# MiniRacer_V2.net
KiCad netlist of a schematic drawn in Altium Designer
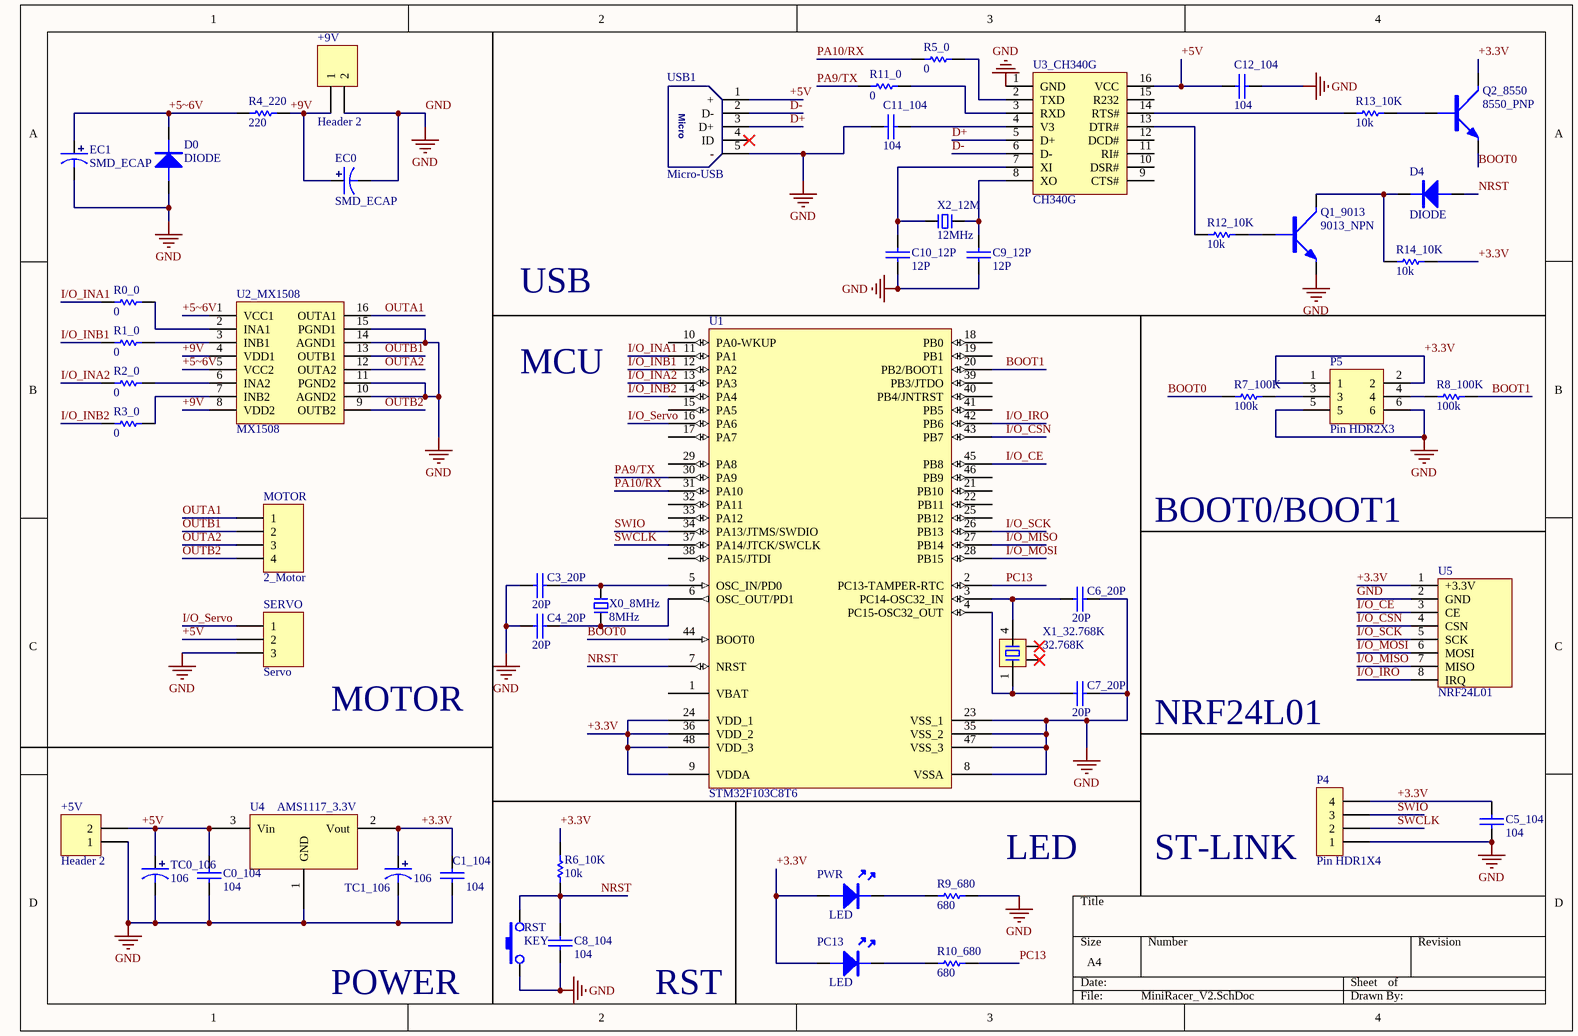
[diagram p0: MiniRacer_V2.SchDoc]

(export (version "E")
  (design (tool "Eeschema 10.0.6"))
  (components
    (comp (ref "+5V")
      (value "Header 2")
      (footprint "HDR1X2")
      (description "Header, 2-Pin")
      (fields (field (name "PUBLISHER") "Altium Limited"))
      (libsource (lib "Miscellaneous Connectors") (part "Header 2"))
    )
    (comp (ref "+9V")
      (value "Header 2")
      (footprint "HDR1X2")
      (description "Header, 2-Pin")
      (fields (field (name "PUBLISHER") "Altium Limited"))
      (libsource (lib "") (part "Header 2_1"))
    )
    (comp (ref "C0_104")
      (value "104")
      (footprint "0603C")
      (description "无极性电容")
      (libsource (lib "电容") (part "CAP"))
    )
    (comp (ref "C1_104")
      (value "104")
      (footprint "0603C")
      (description "无极性电容")
      (libsource (lib "电容") (part "CAP"))
    )
    (comp (ref "C3_20P")
      (value "20P")
      (footprint "0603C")
      (description "无极性电容")
      (libsource (lib "电容") (part "CAP"))
    )
    (comp (ref "C4_20P")
      (value "20P")
      (footprint "0603C")
      (description "无极性电容")
      (libsource (lib "电容") (part "CAP"))
    )
    (comp (ref "C5_104")
      (value "104")
      (footprint "0603C")
      (description "无极性电容")
      (libsource (lib "电容") (part "CAP"))
    )
    (comp (ref "C6_20P")
      (value "20P")
      (footprint "0603C")
      (description "无极性电容")
      (libsource (lib "电容") (part "CAP"))
    )
    (comp (ref "C7_20P")
      (value "20P")
      (footprint "0603C")
      (description "无极性电容")
      (libsource (lib "电容") (part "CAP"))
    )
    (comp (ref "C8_104")
      (value "104")
      (footprint "0603C")
      (description "无极性电容")
      (libsource (lib "电容") (part "CAP"))
    )
    (comp (ref "C9_12P")
      (value "12P")
      (footprint "0603C")
      (description "无极性电容")
      (libsource (lib "电容") (part "CAP"))
    )
    (comp (ref "C10_12P")
      (value "12P")
      (footprint "0603C")
      (description "无极性电容")
      (libsource (lib "电容") (part "CAP"))
    )
    (comp (ref "C11_104")
      (value "104")
      (footprint "0603C")
      (description "无极性电容")
      (libsource (lib "电容") (part "CAP"))
    )
    (comp (ref "C12_104")
      (value "104")
      (footprint "0603C")
      (description "无极性电容")
      (libsource (lib "电容") (part "CAP"))
    )
    (comp (ref "D0")
      (value "DIODE")
      (footprint "LL34")
      (description "普通二极管")
      (libsource (lib "二极管") (part "DIODE"))
    )
    (comp (ref "D4")
      (value "DIODE")
      (footprint "SOD-123")
      (description "普通二极管")
      (libsource (lib "二极管") (part "DIODE"))
    )
    (comp (ref "EC0")
      (value "SMD_ECAP")
      (footprint "SMD-EC6.3X6.3X10")
      (description "贴片电解电容")
      (libsource (lib "电容") (part "SMD_ECAP"))
    )
    (comp (ref "EC1")
      (value "SMD_ECAP")
      (footprint "SMD-EC6.3X6.3X10")
      (description "贴片电解电容")
      (libsource (lib "电容") (part "SMD_ECAP"))
    )
    (comp (ref "MOTOR")
      (value "2_Motor")
      (footprint "HDR1X4")
      (description "Header, 4-Pin")
      (fields (field (name "PUBLISHER") "Altium Limited"))
      (libsource (lib "Miscellaneous Connectors") (part "Header 4"))
    )
    (comp (ref "P4") (value "Pin HDR1X4") (footprint "HDR1X4") (libsource (lib "排针") (part "Pin HDR1X4")))
    (comp (ref "P5")
      (value "Pin HDR2X3")
      (footprint "Pin HDR2X3/2.54mm-S")
      (libsource (lib "排针") (part "Pin HDR2X3"))
    )
    (comp (ref "PC13") (value "LED") (footprint "LED-0603Y") (libsource (lib "LED") (part "LED")))
    (comp (ref "PWR") (value "LED") (footprint "LED-0603Y") (libsource (lib "LED") (part "LED")))
    (comp (ref "Q1_9013")
      (value "9013_NPN")
      (footprint "SOT-23")
      (description "NPN三极管")
      (libsource (lib "三极管") (part "NPN"))
    )
    (comp (ref "Q2_8550")
      (value "8550_PNP")
      (footprint "SOT-23")
      (description "NPN三极管")
      (libsource (lib "三极管") (part "NPN"))
    )
    (comp (ref "R0_0") (value "0") (footprint "0603R") (libsource (lib "电阻") (part "RES")))
    (comp (ref "R1_0") (value "0") (footprint "0603R") (libsource (lib "电阻") (part "RES")))
    (comp (ref "R2_0") (value "0") (footprint "0603R") (libsource (lib "电阻") (part "RES")))
    (comp (ref "R3_0") (value "0") (footprint "0603R") (libsource (lib "电阻") (part "RES")))
    (comp (ref "R4_220") (value "220") (footprint "0603R") (libsource (lib "电阻") (part "RES")))
    (comp (ref "R5_0") (value "0") (footprint "0603R") (libsource (lib "电阻") (part "RES")))
    (comp (ref "R6_10K") (value "10k") (footprint "0603R") (libsource (lib "电阻") (part "RES")))
    (comp (ref "R7_100K") (value "100k") (footprint "0603R") (libsource (lib "电阻") (part "RES")))
    (comp (ref "R8_100K") (value "100k") (footprint "0603R") (libsource (lib "电阻") (part "RES")))
    (comp (ref "R9_680") (value "680") (footprint "0603R") (libsource (lib "电阻") (part "RES")))
    (comp (ref "R10_680") (value "680") (footprint "0603R") (libsource (lib "电阻") (part "RES")))
    (comp (ref "R11_0") (value "0") (footprint "0603R") (libsource (lib "电阻") (part "RES")))
    (comp (ref "R12_10K") (value "10k") (footprint "0603R") (libsource (lib "电阻") (part "RES")))
    (comp (ref "R13_10K") (value "10k") (footprint "0603R") (libsource (lib "电阻") (part "RES")))
    (comp (ref "R14_10K") (value "10k") (footprint "0603R") (libsource (lib "电阻") (part "RES")))
    (comp (ref "RST") (value "KEY") (footprint "SMD-3X6X2.5") (libsource (lib "轻触开关") (part "KEY")))
    (comp (ref "SERVO")
      (value "Servo")
      (footprint "HDR1X3")
      (description "Header, 3-Pin")
      (fields (field (name "PUBLISHER") "Altium Limited"))
      (libsource (lib "Miscellaneous Connectors") (part "Header 3"))
    )
    (comp (ref "TC0_106")
      (value "106")
      (footprint "TAJ-A/3216")
      (description "钽电容")
      (libsource (lib "电容") (part "TCAP"))
    )
    (comp (ref "TC1_106")
      (value "106")
      (footprint "TAJ-A/3216")
      (description "钽电容")
      (libsource (lib "电容") (part "TCAP"))
    )
    (comp (ref "U1")
      (value "STM32F103C8T6")
      (footprint "LQFP48 7X7")
      (libsource (lib "STM32系列") (part "STM32F103C8T6"))
    )
    (comp (ref "U2_MX1508") (value "MX1508") (footprint "SOP16") (libsource (lib "未分类IC") (part "MX1508")))
    (comp (ref "U3_CH340G") (value "CH340G") (footprint "SOP16") (libsource (lib "未分类IC") (part "CH340G")))
    (comp (ref "U4")
      (value "AMS1117_3.3V")
      (footprint "SOT223")
      (description "三端稳压芯片")
      (libsource (lib "电源芯片") (part "AMS1117"))
    )
    (comp (ref "U5") (value "NRF24L01") (footprint "NRF24L01") (libsource (lib "未分类IC") (part "NRF24L01")))
    (comp (ref "USB1")
      (value "Micro-USB")
      (footprint "USB-MICRO_A")
      (libsource (lib "USB") (part "Micro-USB"))
    )
    (comp (ref "X0_8MHz")
      (value "8MHz")
      (footprint "OSC 5032-2P")
      (description "2脚无源脚晶振")
      (libsource (lib "晶振") (part "XTAL-2P"))
    )
    (comp (ref "X1_32.768K")
      (value "32.768K")
      (footprint "OSC MC-306")
      (description "MC系列4脚晶振")
      (libsource (lib "晶振") (part "XTAL-MC-4P"))
    )
    (comp (ref "X2_12M")
      (value "12MHz")
      (footprint "OSC 5032-2P")
      (description "2脚无源脚晶振")
      (libsource (lib "晶振") (part "XTAL-2P"))
    )
  )
  (nets
    (net (code "1") (name "/+3.3V") (class "Default")
      (node (ref "C1_104") (pin "2") (pinfunction "2_2") (pintype "passive"))
      (node (ref "C5_104") (pin "1") (pinfunction "1_1") (pintype "passive"))
      (node (ref "P4") (pin "4") (pinfunction "4_4") (pintype "passive"))
      (node (ref "P5") (pin "1") (pinfunction "1_1") (pintype "passive"))
      (node (ref "P5") (pin "2") (pinfunction "2_2") (pintype "passive"))
      (node (ref "PC13") (pin "A") (pinfunction "A_A") (pintype "passive"))
      (node (ref "PWR") (pin "A") (pinfunction "A_A") (pintype "passive"))
      (node (ref "Q2_8550") (pin "C") (pinfunction "C_C") (pintype "passive"))
      (node (ref "R14_10K") (pin "2") (pinfunction "2_2") (pintype "passive"))
      (node (ref "R6_10K") (pin "2") (pinfunction "2_2") (pintype "passive"))
      (node (ref "TC1_106") (pin "1") (pinfunction "1_1") (pintype "passive"))
      (node (ref "U1") (pin "24") (pinfunction "VDD_1_24") (pintype "power_in"))
      (node (ref "U1") (pin "36") (pinfunction "VDD_2_36") (pintype "power_in"))
      (node (ref "U1") (pin "48") (pinfunction "VDD_3_48") (pintype "power_in"))
      (node (ref "U1") (pin "9") (pinfunction "VDDA_9") (pintype "power_in"))
      (node (ref "U4") (pin "2") (pinfunction "Vout_2") (pintype "passive"))
      (node (ref "U5") (pin "1") (pinfunction "+3.3V_1") (pintype "passive"))
    )
    (net (code "2") (name "/+5V") (class "Default")
      (node (ref "+5V") (pin "2") (pinfunction "2_2") (pintype "passive"))
      (node (ref "C0_104") (pin "2") (pinfunction "2_2") (pintype "passive"))
      (node (ref "C12_104") (pin "2") (pinfunction "2_2") (pintype "passive"))
      (node (ref "SERVO") (pin "2") (pinfunction "2_2") (pintype "passive"))
      (node (ref "TC0_106") (pin "1") (pinfunction "1_1") (pintype "passive"))
      (node (ref "U3_CH340G") (pin "16") (pinfunction "VCC_16") (pintype "passive"))
      (node (ref "U4") (pin "3") (pinfunction "Vin_3") (pintype "passive"))
      (node (ref "USB1") (pin "1") (pinfunction "+_1") (pintype "passive"))
    )
    (net (code "3") (name "/+5~6V") (class "Default")
      (node (ref "D0") (pin "K") (pinfunction "K_K") (pintype "passive"))
      (node (ref "EC1") (pin "1") (pinfunction "1_1") (pintype "passive"))
      (node (ref "R4_220") (pin "1") (pinfunction "1_1") (pintype "passive"))
      (node (ref "U2_MX1508") (pin "1") (pinfunction "VCC1_1") (pintype "passive"))
      (node (ref "U2_MX1508") (pin "5") (pinfunction "VCC2_5") (pintype "passive"))
    )
    (net (code "4") (name "/+9V") (class "Default")
      (node (ref "+9V") (pin "1") (pinfunction "1_1") (pintype "passive"))
      (node (ref "EC0") (pin "1") (pinfunction "1_1") (pintype "passive"))
      (node (ref "R4_220") (pin "2") (pinfunction "2_2") (pintype "passive"))
      (node (ref "U2_MX1508") (pin "4") (pinfunction "VDD1_4") (pintype "passive"))
      (node (ref "U2_MX1508") (pin "8") (pinfunction "VDD2_8") (pintype "passive"))
    )
    (net (code "5") (name "/BOOT0") (class "Default")
      (node (ref "Q2_8550") (pin "E") (pinfunction "E_E") (pintype "passive"))
      (node (ref "R7_100K") (pin "2") (pinfunction "2_2") (pintype "passive"))
      (node (ref "U1") (pin "44") (pinfunction "BOOT0_44") (pintype "input"))
    )
    (net (code "6") (name "/BOOT1") (class "Default")
      (node (ref "R8_100K") (pin "1") (pinfunction "1_1") (pintype "passive"))
      (node (ref "U1") (pin "20") (pinfunction "PB2/BOOT1_20") (pintype "bidirectional"))
    )
    (net (code "7") (name "/D+") (class "Default")
      (node (ref "U3_CH340G") (pin "5") (pinfunction "D+_5") (pintype "passive"))
      (node (ref "USB1") (pin "3") (pinfunction "D+_3") (pintype "passive"))
    )
    (net (code "8") (name "/D-") (class "Default")
      (node (ref "U3_CH340G") (pin "6") (pinfunction "D-_6") (pintype "passive"))
      (node (ref "USB1") (pin "2") (pinfunction "D-_2") (pintype "passive"))
    )
    (net (code "9") (name "/I{slash}O_CE") (class "Default")
      (node (ref "U1") (pin "45") (pinfunction "PB8_45") (pintype "bidirectional"))
      (node (ref "U5") (pin "3") (pinfunction "CE_3") (pintype "passive"))
    )
    (net (code "10") (name "/I{slash}O_CSN") (class "Default")
      (node (ref "U1") (pin "43") (pinfunction "PB7_43") (pintype "bidirectional"))
      (node (ref "U5") (pin "4") (pinfunction "CSN_4") (pintype "passive"))
    )
    (net (code "11") (name "/I{slash}O_INA1") (class "Default")
      (node (ref "R0_0") (pin "1") (pinfunction "1_1") (pintype "passive"))
      (node (ref "U1") (pin "11") (pinfunction "PA1_11") (pintype "bidirectional"))
    )
    (net (code "12") (name "/I{slash}O_INA2") (class "Default")
      (node (ref "R2_0") (pin "1") (pinfunction "1_1") (pintype "passive"))
      (node (ref "U1") (pin "13") (pinfunction "PA3_13") (pintype "bidirectional"))
    )
    (net (code "13") (name "/I{slash}O_INB1") (class "Default")
      (node (ref "R1_0") (pin "1") (pinfunction "1_1") (pintype "passive"))
      (node (ref "U1") (pin "12") (pinfunction "PA2_12") (pintype "bidirectional"))
    )
    (net (code "14") (name "/I{slash}O_INB2") (class "Default")
      (node (ref "R3_0") (pin "1") (pinfunction "1_1") (pintype "passive"))
      (node (ref "U1") (pin "14") (pinfunction "PA4_14") (pintype "bidirectional"))
    )
    (net (code "15") (name "/I{slash}O_IRO") (class "Default")
      (node (ref "U1") (pin "42") (pinfunction "PB6_42") (pintype "bidirectional"))
      (node (ref "U5") (pin "8") (pinfunction "IRQ_8") (pintype "passive"))
    )
    (net (code "16") (name "/I{slash}O_MISO") (class "Default")
      (node (ref "U1") (pin "27") (pinfunction "PB14_27") (pintype "bidirectional"))
      (node (ref "U5") (pin "7") (pinfunction "MISO_7") (pintype "passive"))
    )
    (net (code "17") (name "/I{slash}O_MOSI") (class "Default")
      (node (ref "U1") (pin "28") (pinfunction "PB15_28") (pintype "bidirectional"))
      (node (ref "U5") (pin "6") (pinfunction "MOSI_6") (pintype "passive"))
    )
    (net (code "18") (name "/I{slash}O_SCK") (class "Default")
      (node (ref "U1") (pin "26") (pinfunction "PB13_26") (pintype "bidirectional"))
      (node (ref "U5") (pin "5") (pinfunction "SCK_5") (pintype "passive"))
    )
    (net (code "19") (name "/I{slash}O_Servo") (class "Default")
      (node (ref "SERVO") (pin "1") (pinfunction "1_1") (pintype "passive"))
      (node (ref "U1") (pin "16") (pinfunction "PA6_16") (pintype "bidirectional"))
    )
    (net (code "20") (name "/NRST") (class "Default")
      (node (ref "C8_104") (pin "1") (pinfunction "1_1") (pintype "passive"))
      (node (ref "D4") (pin "A") (pinfunction "A_A") (pintype "passive"))
      (node (ref "R6_10K") (pin "1") (pinfunction "1_1") (pintype "passive"))
      (node (ref "RST") (pin "3") (pinfunction "3_3") (pintype "passive"))
      (node (ref "U1") (pin "7") (pinfunction "NRST_7") (pintype "bidirectional"))
    )
    (net (code "21") (name "/OUTA1") (class "Default")
      (node (ref "MOTOR") (pin "1") (pinfunction "1_1") (pintype "passive"))
      (node (ref "U2_MX1508") (pin "16") (pinfunction "OUTA1_16") (pintype "passive"))
    )
    (net (code "22") (name "/OUTA2") (class "Default")
      (node (ref "MOTOR") (pin "3") (pinfunction "3_3") (pintype "passive"))
      (node (ref "U2_MX1508") (pin "12") (pinfunction "OUTA2_12") (pintype "passive"))
    )
    (net (code "23") (name "/OUTB1") (class "Default")
      (node (ref "MOTOR") (pin "2") (pinfunction "2_2") (pintype "passive"))
      (node (ref "U2_MX1508") (pin "13") (pinfunction "OUTB1_13") (pintype "passive"))
    )
    (net (code "24") (name "/OUTB2") (class "Default")
      (node (ref "MOTOR") (pin "4") (pinfunction "4_4") (pintype "passive"))
      (node (ref "U2_MX1508") (pin "9") (pinfunction "OUTB2_9") (pintype "passive"))
    )
    (net (code "25") (name "/PA9{slash}TX") (class "Default")
      (node (ref "R11_0") (pin "1") (pinfunction "1_1") (pintype "passive"))
      (node (ref "U1") (pin "30") (pinfunction "PA9_30") (pintype "bidirectional"))
    )
    (net (code "26") (name "/PA10{slash}RX") (class "Default")
      (node (ref "R5_0") (pin "1") (pinfunction "1_1") (pintype "passive"))
      (node (ref "U1") (pin "31") (pinfunction "PA10_31") (pintype "bidirectional"))
    )
    (net (code "27") (name "/PC13") (class "Default")
      (node (ref "R10_680") (pin "1") (pinfunction "1_1") (pintype "passive"))
      (node (ref "U1") (pin "2") (pinfunction "PC13-TAMPER-RTC_2") (pintype "bidirectional"))
    )
    (net (code "28") (name "/SWCLK") (class "Default")
      (node (ref "P4") (pin "2") (pinfunction "2_2") (pintype "passive"))
      (node (ref "U1") (pin "37") (pinfunction "PA14/JTCK/SWCLK_37") (pintype "bidirectional"))
    )
    (net (code "29") (name "/SWIO") (class "Default")
      (node (ref "P4") (pin "3") (pinfunction "3_3") (pintype "passive"))
      (node (ref "U1") (pin "34") (pinfunction "PA13/JTMS/SWDIO_34") (pintype "bidirectional"))
    )
    (net (code "30") (name "GND") (class "Default")
      (node (ref "+5V") (pin "1") (pinfunction "1_1") (pintype "passive"))
      (node (ref "+9V") (pin "2") (pinfunction "2_2") (pintype "passive"))
      (node (ref "C0_104") (pin "1") (pinfunction "1_1") (pintype "passive"))
      (node (ref "C10_12P") (pin "2") (pinfunction "2_2") (pintype "passive"))
      (node (ref "C11_104") (pin "2") (pinfunction "2_2") (pintype "passive"))
      (node (ref "C12_104") (pin "1") (pinfunction "1_1") (pintype "passive"))
      (node (ref "C1_104") (pin "1") (pinfunction "1_1") (pintype "passive"))
      (node (ref "C3_20P") (pin "2") (pinfunction "2_2") (pintype "passive"))
      (node (ref "C4_20P") (pin "2") (pinfunction "2_2") (pintype "passive"))
      (node (ref "C5_104") (pin "2") (pinfunction "2_2") (pintype "passive"))
      (node (ref "C6_20P") (pin "1") (pinfunction "1_1") (pintype "passive"))
      (node (ref "C7_20P") (pin "1") (pinfunction "1_1") (pintype "passive"))
      (node (ref "C8_104") (pin "2") (pinfunction "2_2") (pintype "passive"))
      (node (ref "C9_12P") (pin "2") (pinfunction "2_2") (pintype "passive"))
      (node (ref "D0") (pin "A") (pinfunction "A_A") (pintype "passive"))
      (node (ref "EC0") (pin "2") (pinfunction "2_2") (pintype "passive"))
      (node (ref "EC1") (pin "2") (pinfunction "2_2") (pintype "passive"))
      (node (ref "P4") (pin "1") (pinfunction "1_1") (pintype "passive"))
      (node (ref "P5") (pin "5") (pinfunction "5_5") (pintype "passive"))
      (node (ref "P5") (pin "6") (pinfunction "6_6") (pintype "passive"))
      (node (ref "Q1_9013") (pin "E") (pinfunction "E_E") (pintype "passive"))
      (node (ref "R9_680") (pin "1") (pinfunction "1_1") (pintype "passive"))
      (node (ref "RST") (pin "1") (pinfunction "1_1") (pintype "passive"))
      (node (ref "SERVO") (pin "3") (pinfunction "3_3") (pintype "passive"))
      (node (ref "TC0_106") (pin "2") (pinfunction "2_2") (pintype "passive"))
      (node (ref "TC1_106") (pin "2") (pinfunction "2_2") (pintype "passive"))
      (node (ref "U1") (pin "23") (pinfunction "VSS_1_23") (pintype "power_in"))
      (node (ref "U1") (pin "35") (pinfunction "VSS_2_35") (pintype "power_in"))
      (node (ref "U1") (pin "47") (pinfunction "VSS_3_47") (pintype "power_in"))
      (node (ref "U1") (pin "8") (pinfunction "VSSA_8") (pintype "power_in"))
      (node (ref "U2_MX1508") (pin "10") (pinfunction "AGND2_10") (pintype "passive"))
      (node (ref "U2_MX1508") (pin "11") (pinfunction "PGND2_11") (pintype "passive"))
      (node (ref "U2_MX1508") (pin "14") (pinfunction "AGND1_14") (pintype "passive"))
      (node (ref "U2_MX1508") (pin "15") (pinfunction "PGND1_15") (pintype "passive"))
      (node (ref "U3_CH340G") (pin "1") (pinfunction "GND_1") (pintype "passive"))
      (node (ref "U4") (pin "1") (pinfunction "GND_1") (pintype "passive"))
      (node (ref "U5") (pin "2") (pinfunction "GND_2") (pintype "passive"))
      (node (ref "USB1") (pin "5") (pinfunction "-_5") (pintype "passive"))
    )
    (net (code "31") (name "Net-(D4-PadK)") (class "Default")
      (node (ref "D4") (pin "K") (pinfunction "K_K") (pintype "passive"))
      (node (ref "Q1_9013") (pin "C") (pinfunction "C_C") (pintype "passive"))
      (node (ref "R14_10K") (pin "1") (pinfunction "1_1") (pintype "passive"))
    )
    (net (code "32") (name "Net-(P5-Pad3)") (class "Default")
      (node (ref "P5") (pin "3") (pinfunction "3_3") (pintype "passive"))
      (node (ref "R7_100K") (pin "1") (pinfunction "1_1") (pintype "passive"))
    )
    (net (code "33") (name "Net-(P5-Pad4)") (class "Default")
      (node (ref "P5") (pin "4") (pinfunction "4_4") (pintype "passive"))
      (node (ref "R8_100K") (pin "2") (pinfunction "2_2") (pintype "passive"))
    )
    (net (code "34") (name "Net-(PC13-PadK)") (class "Default")
      (node (ref "PC13") (pin "K") (pinfunction "K_K") (pintype "passive"))
      (node (ref "R10_680") (pin "2") (pinfunction "2_2") (pintype "passive"))
    )
    (net (code "35") (name "Net-(PWR-PadK)") (class "Default")
      (node (ref "PWR") (pin "K") (pinfunction "K_K") (pintype "passive"))
      (node (ref "R9_680") (pin "2") (pinfunction "2_2") (pintype "passive"))
    )
    (net (code "36") (name "Net-(Q1_9013-PadB)") (class "Default")
      (node (ref "Q1_9013") (pin "B") (pinfunction "B_B") (pintype "passive"))
      (node (ref "R12_10K") (pin "2") (pinfunction "2_2") (pintype "passive"))
    )
    (net (code "37") (name "Net-(Q2_8550-PadB)") (class "Default")
      (node (ref "Q2_8550") (pin "B") (pinfunction "B_B") (pintype "passive"))
      (node (ref "R13_10K") (pin "2") (pinfunction "2_2") (pintype "passive"))
    )
    (net (code "38") (name "Net-(U1-OSC_IN{slash}PD0)") (class "Default")
      (node (ref "C3_20P") (pin "1") (pinfunction "1_1") (pintype "passive"))
      (node (ref "U1") (pin "5") (pinfunction "OSC_IN/PD0_5") (pintype "input"))
      (node (ref "X0_8MHz") (pin "2") (pinfunction "2_2") (pintype "passive"))
    )
    (net (code "39") (name "Net-(U1-OSC_OUT{slash}PD1)") (class "Default")
      (node (ref "C4_20P") (pin "1") (pinfunction "1_1") (pintype "passive"))
      (node (ref "U1") (pin "6") (pinfunction "OSC_OUT/PD1_6") (pintype "output"))
      (node (ref "X0_8MHz") (pin "1") (pinfunction "1_1") (pintype "passive"))
    )
    (net (code "40") (name "Net-(U1-PC14-OSC32_IN)") (class "Default")
      (node (ref "C6_20P") (pin "2") (pinfunction "2_2") (pintype "passive"))
      (node (ref "U1") (pin "3") (pinfunction "PC14-OSC32_IN_3") (pintype "bidirectional"))
      (node (ref "X1_32.768K") (pin "4") (pinfunction "4_4") (pintype "passive"))
    )
    (net (code "41") (name "Net-(U1-PC15-OSC32_OUT)") (class "Default")
      (node (ref "C7_20P") (pin "2") (pinfunction "2_2") (pintype "passive"))
      (node (ref "U1") (pin "4") (pinfunction "PC15-OSC32_OUT_4") (pintype "bidirectional"))
      (node (ref "X1_32.768K") (pin "1") (pinfunction "1_1") (pintype "passive"))
    )
    (net (code "42") (name "Net-(U2_MX1508-INA1)") (class "Default")
      (node (ref "R0_0") (pin "2") (pinfunction "2_2") (pintype "passive"))
      (node (ref "U2_MX1508") (pin "2") (pinfunction "INA1_2") (pintype "passive"))
    )
    (net (code "43") (name "Net-(U2_MX1508-INA2)") (class "Default")
      (node (ref "R2_0") (pin "2") (pinfunction "2_2") (pintype "passive"))
      (node (ref "U2_MX1508") (pin "6") (pinfunction "INA2_6") (pintype "passive"))
    )
    (net (code "44") (name "Net-(U2_MX1508-INB1)") (class "Default")
      (node (ref "R1_0") (pin "2") (pinfunction "2_2") (pintype "passive"))
      (node (ref "U2_MX1508") (pin "3") (pinfunction "INB1_3") (pintype "passive"))
    )
    (net (code "45") (name "Net-(U2_MX1508-INB2)") (class "Default")
      (node (ref "R3_0") (pin "2") (pinfunction "2_2") (pintype "passive"))
      (node (ref "U2_MX1508") (pin "7") (pinfunction "INB2_7") (pintype "passive"))
    )
    (net (code "46") (name "Net-(U3_CH340G-DTR#)") (class "Default")
      (node (ref "R12_10K") (pin "1") (pinfunction "1_1") (pintype "passive"))
      (node (ref "U3_CH340G") (pin "13") (pinfunction "DTR#_13") (pintype "passive"))
    )
    (net (code "47") (name "Net-(U3_CH340G-RTS#)") (class "Default")
      (node (ref "R13_10K") (pin "1") (pinfunction "1_1") (pintype "passive"))
      (node (ref "U3_CH340G") (pin "14") (pinfunction "RTS#_14") (pintype "passive"))
    )
    (net (code "48") (name "Net-(U3_CH340G-RXD)") (class "Default")
      (node (ref "R11_0") (pin "2") (pinfunction "2_2") (pintype "passive"))
      (node (ref "U3_CH340G") (pin "3") (pinfunction "RXD_3") (pintype "passive"))
    )
    (net (code "49") (name "Net-(U3_CH340G-TXD)") (class "Default")
      (node (ref "R5_0") (pin "2") (pinfunction "2_2") (pintype "passive"))
      (node (ref "U3_CH340G") (pin "2") (pinfunction "TXD_2") (pintype "passive"))
    )
    (net (code "50") (name "Net-(U3_CH340G-V3)") (class "Default")
      (node (ref "C11_104") (pin "1") (pinfunction "1_1") (pintype "passive"))
      (node (ref "U3_CH340G") (pin "4") (pinfunction "V3_4") (pintype "passive"))
    )
    (net (code "51") (name "Net-(U3_CH340G-XI)") (class "Default")
      (node (ref "C10_12P") (pin "1") (pinfunction "1_1") (pintype "passive"))
      (node (ref "U3_CH340G") (pin "7") (pinfunction "XI_7") (pintype "passive"))
      (node (ref "X2_12M") (pin "2") (pinfunction "2_2") (pintype "passive"))
    )
    (net (code "52") (name "Net-(U3_CH340G-XO)") (class "Default")
      (node (ref "C9_12P") (pin "1") (pinfunction "1_1") (pintype "passive"))
      (node (ref "U3_CH340G") (pin "8") (pinfunction "XO_8") (pintype "passive"))
      (node (ref "X2_12M") (pin "1") (pinfunction "1_1") (pintype "passive"))
    )
    (net (code "53") (name "unconnected-(U1-PA0-WKUP-Pad10)") (class "Default")
      (node (ref "U1") (pin "10") (pinfunction "PA0-WKUP_10") (pintype "bidirectional"))
    )
    (net (code "54") (name "unconnected-(U1-PA5-Pad15)") (class "Default")
      (node (ref "U1") (pin "15") (pinfunction "PA5_15") (pintype "bidirectional"))
    )
    (net (code "55") (name "unconnected-(U1-PA7-Pad17)") (class "Default")
      (node (ref "U1") (pin "17") (pinfunction "PA7_17") (pintype "bidirectional"))
    )
    (net (code "56") (name "unconnected-(U1-PA8-Pad29)") (class "Default")
      (node (ref "U1") (pin "29") (pinfunction "PA8_29") (pintype "bidirectional"))
    )
    (net (code "57") (name "unconnected-(U1-PA11-Pad32)") (class "Default")
      (node (ref "U1") (pin "32") (pinfunction "PA11_32") (pintype "bidirectional"))
    )
    (net (code "58") (name "unconnected-(U1-PA12-Pad33)") (class "Default")
      (node (ref "U1") (pin "33") (pinfunction "PA12_33") (pintype "bidirectional"))
    )
    (net (code "59") (name "unconnected-(U1-PA15{slash}JTDI-Pad38)") (class "Default")
      (node (ref "U1") (pin "38") (pinfunction "PA15/JTDI_38") (pintype "bidirectional"))
    )
    (net (code "60") (name "unconnected-(U1-PB0-Pad18)") (class "Default")
      (node (ref "U1") (pin "18") (pinfunction "PB0_18") (pintype "bidirectional"))
    )
    (net (code "61") (name "unconnected-(U1-PB1-Pad19)") (class "Default")
      (node (ref "U1") (pin "19") (pinfunction "PB1_19") (pintype "bidirectional"))
    )
    (net (code "62") (name "unconnected-(U1-PB3{slash}JTDO-Pad39)") (class "Default")
      (node (ref "U1") (pin "39") (pinfunction "PB3/JTDO_39") (pintype "bidirectional"))
    )
    (net (code "63") (name "unconnected-(U1-PB4{slash}JNTRST-Pad40)") (class "Default")
      (node (ref "U1") (pin "40") (pinfunction "PB4/JNTRST_40") (pintype "bidirectional"))
    )
    (net (code "64") (name "unconnected-(U1-PB5-Pad41)") (class "Default")
      (node (ref "U1") (pin "41") (pinfunction "PB5_41") (pintype "bidirectional"))
    )
    (net (code "65") (name "unconnected-(U1-PB9-Pad46)") (class "Default")
      (node (ref "U1") (pin "46") (pinfunction "PB9_46") (pintype "bidirectional"))
    )
    (net (code "66") (name "unconnected-(U1-PB10-Pad21)") (class "Default")
      (node (ref "U1") (pin "21") (pinfunction "PB10_21") (pintype "bidirectional"))
    )
    (net (code "67") (name "unconnected-(U1-PB11-Pad22)") (class "Default")
      (node (ref "U1") (pin "22") (pinfunction "PB11_22") (pintype "bidirectional"))
    )
    (net (code "68") (name "unconnected-(U1-PB12-Pad25)") (class "Default")
      (node (ref "U1") (pin "25") (pinfunction "PB12_25") (pintype "bidirectional"))
    )
    (net (code "69") (name "unconnected-(U1-VBAT-Pad1)") (class "Default")
      (node (ref "U1") (pin "1") (pinfunction "VBAT_1") (pintype "power_in"))
    )
    (net (code "70") (name "unconnected-(U3_CH340G-CTS#-Pad9)") (class "Default")
      (node (ref "U3_CH340G") (pin "9") (pinfunction "CTS#_9") (pintype "passive"))
    )
    (net (code "71") (name "unconnected-(U3_CH340G-DCD#-Pad12)") (class "Default")
      (node (ref "U3_CH340G") (pin "12") (pinfunction "DCD#_12") (pintype "passive"))
    )
    (net (code "72") (name "unconnected-(U3_CH340G-DSR#-Pad10)") (class "Default")
      (node (ref "U3_CH340G") (pin "10") (pinfunction "DSR#_10") (pintype "passive"))
    )
    (net (code "73") (name "unconnected-(U3_CH340G-R232-Pad15)") (class "Default")
      (node (ref "U3_CH340G") (pin "15") (pinfunction "R232_15") (pintype "passive"))
    )
    (net (code "74") (name "unconnected-(U3_CH340G-RI#-Pad11)") (class "Default")
      (node (ref "U3_CH340G") (pin "11") (pinfunction "RI#_11") (pintype "passive"))
    )
    (net (code "75") (name "unconnected-(USB1-ID-Pad4)") (class "Default")
      (node (ref "USB1") (pin "4") (pinfunction "ID_4") (pintype "passive+no_connect"))
    )
    (net (code "76") (name "unconnected-(X1_32.768K-Pad2)") (class "Default")
      (node (ref "X1_32.768K") (pin "2") (pinfunction "2_2") (pintype "passive+no_connect"))
    )
    (net (code "77") (name "unconnected-(X1_32.768K-Pad3)") (class "Default")
      (node (ref "X1_32.768K") (pin "3") (pinfunction "3_3") (pintype "passive+no_connect"))
    )
  )
)
